# SMPS.net
KiCad netlist of a schematic drawn in Altium Designer
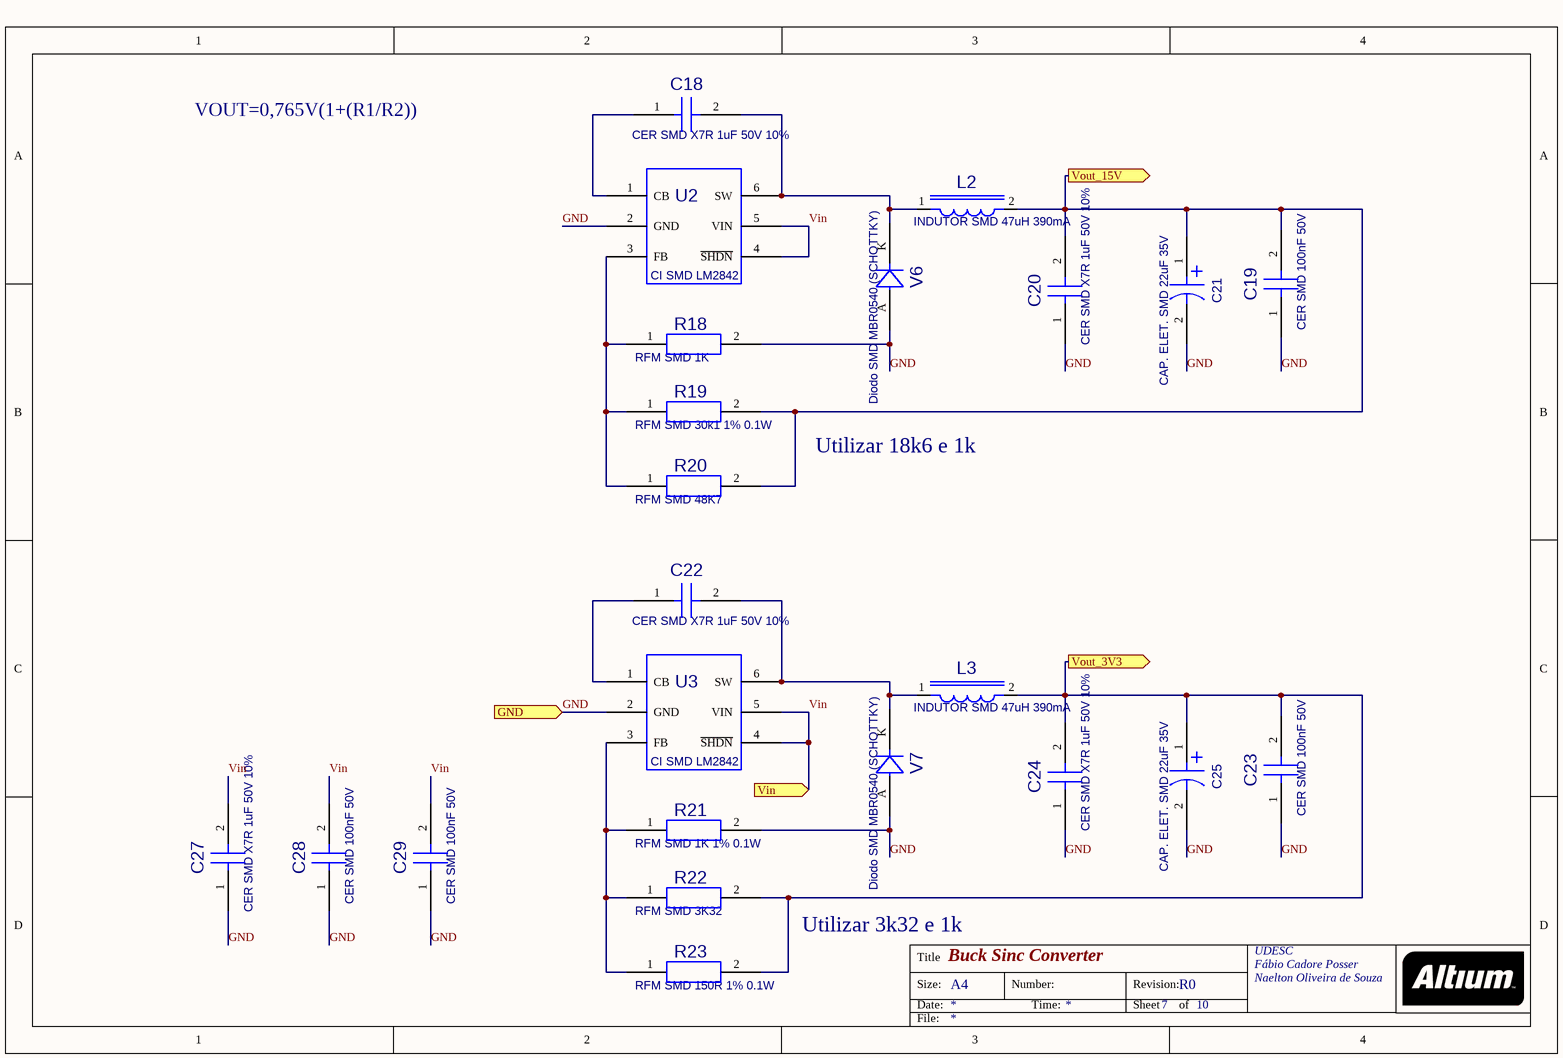
[diagram p0: SMPS.SchDoc]

(export (version "E")
  (design (tool "Eeschema 10.0.6"))
  (components
    (comp (ref "C18")
      (value "CER SMD X7R 1uF 50V 10%")
      (footprint "C0805_R_V0")
      (fields (field (name "Comment") "11736520"))
      (libsource (lib "Conv_buck_R0") (part "11736520"))
    )
    (comp (ref "C19")
      (value "CER SMD 100nF 50V")
      (footprint "C0805_R_V0")
      (fields (field (name "Comment") "10192075"))
      (libsource (lib "Conv_buck_R0") (part "10192075"))
    )
    (comp (ref "C20")
      (value "CER SMD X7R 1uF 50V 10%")
      (footprint "C0805_R_V0")
      (fields (field (name "Comment") "11736520"))
      (libsource (lib "Conv_buck_R0") (part "11736520"))
    )
    (comp (ref "C21")
      (value "CAP. ELET. SMD 22uF 35V")
      (footprint "CAP UUD CR 5X5.8")
      (fields (field (name "Comment") "11690909"))
      (libsource (lib "Conv_buck_R0") (part "11690909"))
    )
    (comp (ref "C22")
      (value "CER SMD X7R 1uF 50V 10%")
      (footprint "C0805_R_V0")
      (fields (field (name "Comment") "11736520"))
      (libsource (lib "Conv_buck_R0") (part "11736520"))
    )
    (comp (ref "C23")
      (value "CER SMD 100nF 50V")
      (footprint "C0805_R_V0")
      (fields (field (name "Comment") "10192075"))
      (libsource (lib "Conv_buck_R0") (part "10192075"))
    )
    (comp (ref "C24")
      (value "CER SMD X7R 1uF 50V 10%")
      (footprint "C0805_R_V0")
      (fields (field (name "Comment") "11736520"))
      (libsource (lib "Conv_buck_R0") (part "11736520"))
    )
    (comp (ref "C25")
      (value "CAP. ELET. SMD 22uF 35V")
      (footprint "CAP UUD CR 5X5.8")
      (fields (field (name "Comment") "11690909"))
      (libsource (lib "Conv_buck_R0") (part "11690909"))
    )
    (comp (ref "C27")
      (value "CER SMD X7R 1uF 50V 10%")
      (footprint "C0805_R_V0")
      (fields (field (name "Comment") "11736520"))
      (libsource (lib "Conv_buck_R0") (part "11736520"))
    )
    (comp (ref "C28")
      (value "CER SMD 100nF 50V")
      (footprint "C0805_R_V0")
      (fields (field (name "Comment") "10192075"))
      (libsource (lib "Conv_buck_R0") (part "10192075"))
    )
    (comp (ref "C29")
      (value "CER SMD 100nF 50V")
      (footprint "C0805_R_V0")
      (fields (field (name "Comment") "10192075"))
      (libsource (lib "Conv_buck_R0") (part "10192075"))
    )
    (comp (ref "L2")
      (value "INDUTOR SMD 47uH 390mA")
      (footprint "L1210")
      (fields (field (name "Comment") "12924787"))
      (libsource (lib "Conv_buck_R0") (part "12924787"))
    )
    (comp (ref "L3")
      (value "INDUTOR SMD 47uH 390mA")
      (footprint "L1210")
      (fields (field (name "Comment") "12924787"))
      (libsource (lib "Conv_buck_R0") (part "12924787"))
    )
    (comp (ref "R18")
      (value "RFM SMD 1K")
      (footprint "R0805_R_V0")
      (fields (field (name "Comment") "10118077"))
      (libsource (lib "Conv_buck_R0") (part "10191981"))
    )
    (comp (ref "R19")
      (value "RFM SMD 30k1 1% 0.1W")
      (footprint "R0805_R_V0")
      (fields (field (name "Comment") "10191986"))
      (libsource (lib "Conv_buck_R0") (part "10191981"))
    )
    (comp (ref "R20")
      (value "RFM SMD 48K7")
      (footprint "R0805_R_V0")
      (fields (field (name "Comment") "10192020"))
      (libsource (lib "Conv_buck_R0") (part "10191981"))
    )
    (comp (ref "R21")
      (value "RFM SMD 1K 1% 0.1W")
      (footprint "R0805_R_V0")
      (fields (field (name "Comment") "10118077"))
      (libsource (lib "Conv_buck_R0") (part "10191981"))
    )
    (comp (ref "R22")
      (value "RFM SMD 3K32")
      (footprint "R0805_R_V0")
      (fields (field (name "Comment") "10191979"))
      (libsource (lib "Conv_buck_R0") (part "10191981"))
    )
    (comp (ref "R23")
      (value "RFM SMD 150R 1% 0.1W")
      (footprint "R0805_R_V0")
      (fields (field (name "Comment") "10191981"))
      (libsource (lib "Conv_buck_R0") (part "10191981"))
    )
    (comp (ref "U2")
      (value "CI SMD LM2842")
      (footprint "SOT23-6")
      (fields (field (name "Comment") "12576507"))
      (libsource (lib "Conv_buck_R0") (part "12576507"))
    )
    (comp (ref "U3")
      (value "CI SMD LM2842")
      (footprint "SOT23-6")
      (fields (field (name "Comment") "12576507"))
      (libsource (lib "Conv_buck_R0") (part "12576507"))
    )
    (comp (ref "V6")
      (value "Diodo SMD MBR0540 (SCHOTTKY)")
      (footprint "SOD123A")
      (fields (field (name "Comment") "10192125"))
      (libsource (lib "Conv_buck_R0") (part "10192125"))
    )
    (comp (ref "V7")
      (value "Diodo SMD MBR0540 (SCHOTTKY)")
      (footprint "SOD123A")
      (fields (field (name "Comment") "10192125"))
      (libsource (lib "Conv_buck_R0") (part "10192125"))
    )
  )
  (nets
    (net (code "1") (name "/GND") (class "Default")
      (node (ref "C19") (pin "1") (pinfunction "1_1") (pintype "passive"))
      (node (ref "C20") (pin "1") (pinfunction "1_1") (pintype "passive"))
      (node (ref "C21") (pin "2") (pinfunction "2_2") (pintype "passive"))
      (node (ref "C23") (pin "1") (pinfunction "1_1") (pintype "passive"))
      (node (ref "C24") (pin "1") (pinfunction "1_1") (pintype "passive"))
      (node (ref "C25") (pin "2") (pinfunction "2_2") (pintype "passive"))
      (node (ref "C27") (pin "1") (pinfunction "1_1") (pintype "passive"))
      (node (ref "C28") (pin "1") (pinfunction "1_1") (pintype "passive"))
      (node (ref "C29") (pin "1") (pinfunction "1_1") (pintype "passive"))
      (node (ref "R18") (pin "2") (pinfunction "2_2") (pintype "passive"))
      (node (ref "R21") (pin "2") (pinfunction "2_2") (pintype "passive"))
      (node (ref "U2") (pin "2") (pinfunction "GND_2") (pintype "passive"))
      (node (ref "U3") (pin "2") (pinfunction "GND_2") (pintype "passive"))
      (node (ref "V6") (pin "A") (pinfunction "A_A") (pintype "passive"))
      (node (ref "V7") (pin "A") (pinfunction "A_A") (pintype "passive"))
    )
    (net (code "2") (name "/Vin") (class "Default")
      (node (ref "C27") (pin "2") (pinfunction "2_2") (pintype "passive"))
      (node (ref "C28") (pin "2") (pinfunction "2_2") (pintype "passive"))
      (node (ref "C29") (pin "2") (pinfunction "2_2") (pintype "passive"))
      (node (ref "U2") (pin "4") (pinfunction "~{SHDN}_4") (pintype "passive"))
      (node (ref "U2") (pin "5") (pinfunction "VIN_5") (pintype "passive"))
      (node (ref "U3") (pin "4") (pinfunction "~{SHDN}_4") (pintype "passive"))
      (node (ref "U3") (pin "5") (pinfunction "VIN_5") (pintype "passive"))
    )
    (net (code "3") (name "/Vout_3V3") (class "Default")
      (node (ref "C23") (pin "2") (pinfunction "2_2") (pintype "passive"))
      (node (ref "C24") (pin "2") (pinfunction "2_2") (pintype "passive"))
      (node (ref "C25") (pin "1") (pinfunction "1_1") (pintype "passive"))
      (node (ref "L3") (pin "2") (pinfunction "2_2") (pintype "passive"))
      (node (ref "R22") (pin "2") (pinfunction "2_2") (pintype "passive"))
      (node (ref "R23") (pin "2") (pinfunction "2_2") (pintype "passive"))
    )
    (net (code "4") (name "/Vout_15V") (class "Default")
      (node (ref "C19") (pin "2") (pinfunction "2_2") (pintype "passive"))
      (node (ref "C20") (pin "2") (pinfunction "2_2") (pintype "passive"))
      (node (ref "C21") (pin "1") (pinfunction "1_1") (pintype "passive"))
      (node (ref "L2") (pin "2") (pinfunction "2_2") (pintype "passive"))
      (node (ref "R19") (pin "2") (pinfunction "2_2") (pintype "passive"))
      (node (ref "R20") (pin "2") (pinfunction "2_2") (pintype "passive"))
    )
    (net (code "5") (name "Net-(U2-CB)") (class "Default")
      (node (ref "C18") (pin "1") (pinfunction "1_1") (pintype "passive"))
      (node (ref "U2") (pin "1") (pinfunction "CB_1") (pintype "passive"))
    )
    (net (code "6") (name "Net-(U2-FB)") (class "Default")
      (node (ref "R18") (pin "1") (pinfunction "1_1") (pintype "passive"))
      (node (ref "R19") (pin "1") (pinfunction "1_1") (pintype "passive"))
      (node (ref "R20") (pin "1") (pinfunction "1_1") (pintype "passive"))
      (node (ref "U2") (pin "3") (pinfunction "FB_3") (pintype "passive"))
    )
    (net (code "7") (name "Net-(U2-SW)") (class "Default")
      (node (ref "C18") (pin "2") (pinfunction "2_2") (pintype "passive"))
      (node (ref "L2") (pin "1") (pinfunction "1_1") (pintype "passive"))
      (node (ref "U2") (pin "6") (pinfunction "SW_6") (pintype "passive"))
      (node (ref "V6") (pin "K") (pinfunction "K_K") (pintype "passive"))
    )
    (net (code "8") (name "Net-(U3-CB)") (class "Default")
      (node (ref "C22") (pin "1") (pinfunction "1_1") (pintype "passive"))
      (node (ref "U3") (pin "1") (pinfunction "CB_1") (pintype "passive"))
    )
    (net (code "9") (name "Net-(U3-FB)") (class "Default")
      (node (ref "R21") (pin "1") (pinfunction "1_1") (pintype "passive"))
      (node (ref "R22") (pin "1") (pinfunction "1_1") (pintype "passive"))
      (node (ref "R23") (pin "1") (pinfunction "1_1") (pintype "passive"))
      (node (ref "U3") (pin "3") (pinfunction "FB_3") (pintype "passive"))
    )
    (net (code "10") (name "Net-(U3-SW)") (class "Default")
      (node (ref "C22") (pin "2") (pinfunction "2_2") (pintype "passive"))
      (node (ref "L3") (pin "1") (pinfunction "1_1") (pintype "passive"))
      (node (ref "U3") (pin "6") (pinfunction "SW_6") (pintype "passive"))
      (node (ref "V7") (pin "K") (pinfunction "K_K") (pintype "passive"))
    )
  )
)
